# chariot_sensor.net
KiCad netlist of a schematic drawn in EAGLE
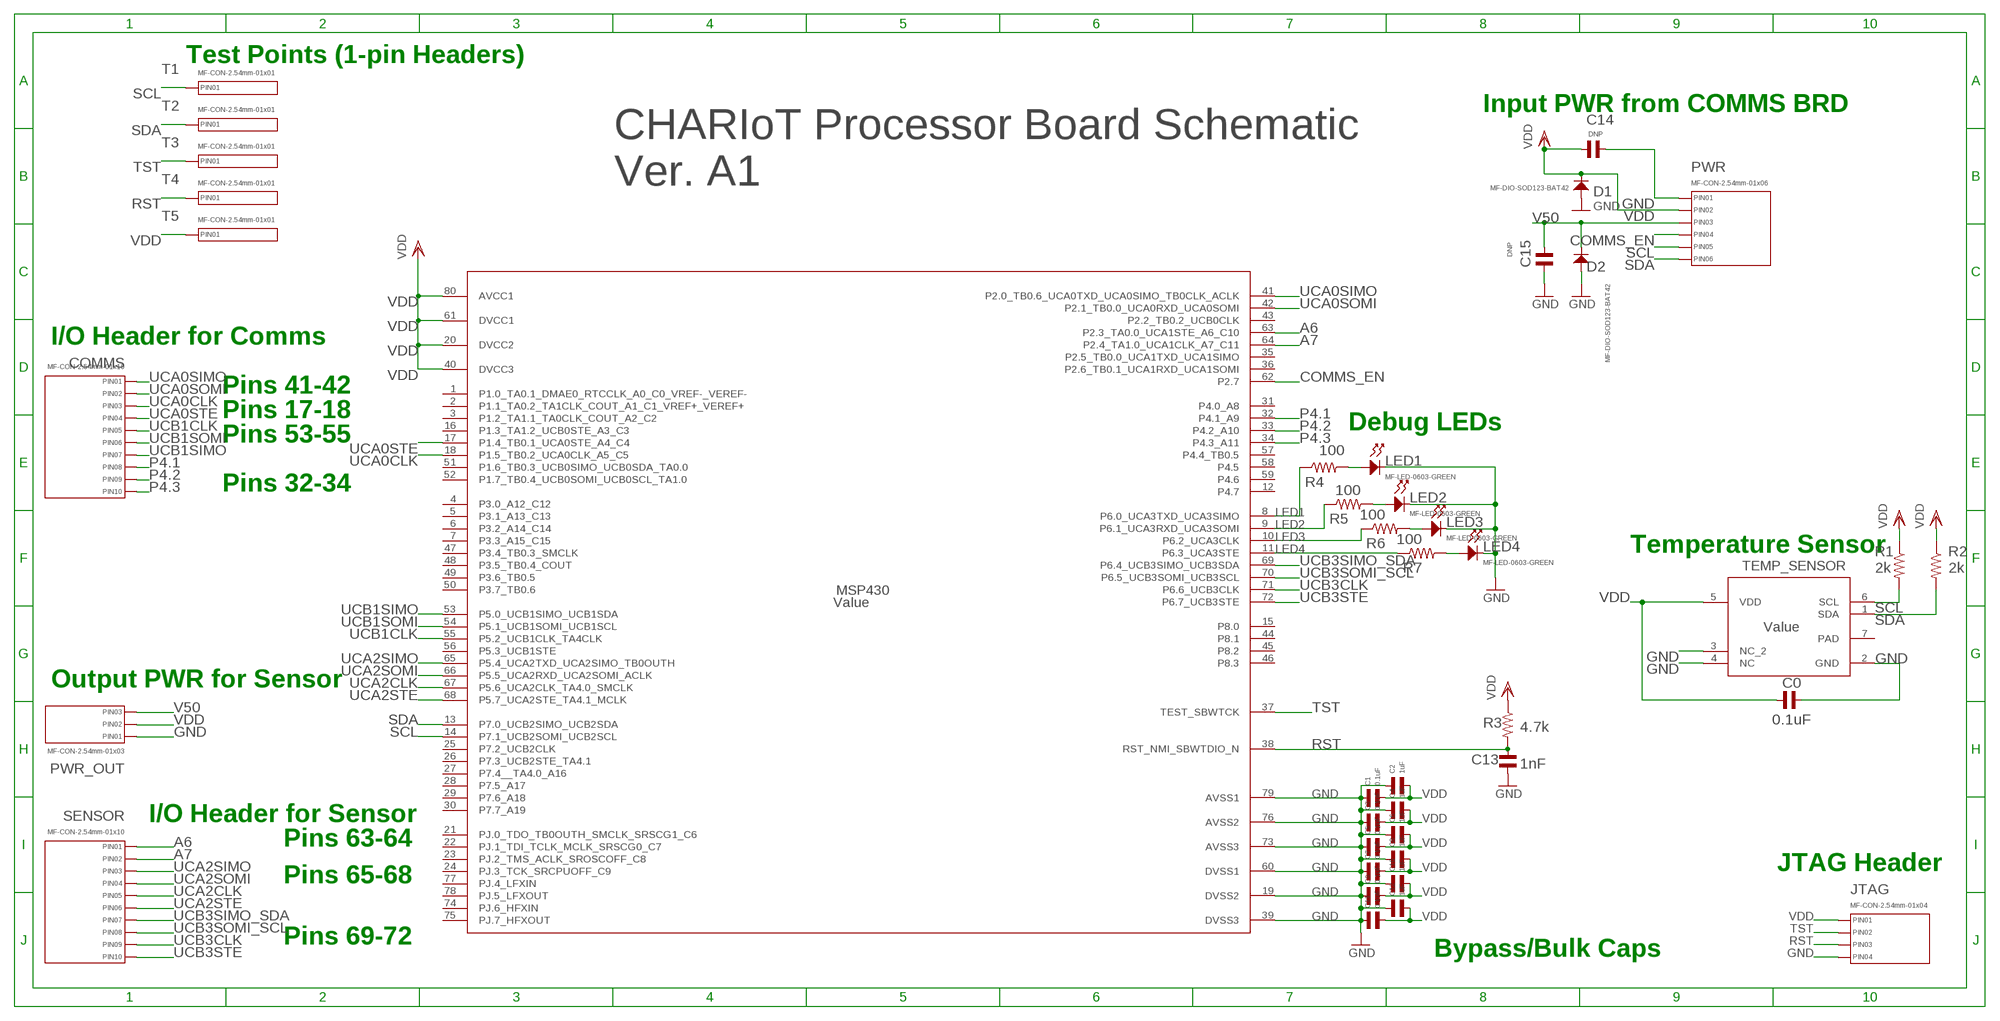
[diagram p0: schematic, sheet 1]

(export (version "E")
  (design (tool "Eeschema 10.0.6"))
  (components
    (comp (ref "C0")
      (value "0.1uF")
      (footprint "eagle-import:C0603")
      (libsource (lib "eagle-import") (part "CAPACITOR_NP_0603"))
    )
    (comp (ref "C1")
      (value "0.1uF")
      (footprint "eagle-import:C0603")
      (libsource (lib "eagle-import") (part "CAPACITOR_NP_0603"))
    )
    (comp (ref "C2")
      (value "1uF")
      (footprint "eagle-import:C0603")
      (libsource (lib "eagle-import") (part "CAPACITOR_NP_0603"))
    )
    (comp (ref "C3")
      (value "0.1uF")
      (footprint "eagle-import:C0603")
      (libsource (lib "eagle-import") (part "CAPACITOR_NP_0603"))
    )
    (comp (ref "C4")
      (value "1uF")
      (footprint "eagle-import:C0603")
      (libsource (lib "eagle-import") (part "CAPACITOR_NP_0603"))
    )
    (comp (ref "C5")
      (value "0.1uF")
      (footprint "eagle-import:C0603")
      (libsource (lib "eagle-import") (part "CAPACITOR_NP_0603"))
    )
    (comp (ref "C6")
      (value "1uF")
      (footprint "eagle-import:C0603")
      (libsource (lib "eagle-import") (part "CAPACITOR_NP_0603"))
    )
    (comp (ref "C7")
      (value "0.1uF")
      (footprint "eagle-import:C0603")
      (libsource (lib "eagle-import") (part "CAPACITOR_NP_0603"))
    )
    (comp (ref "C8")
      (value "1uF")
      (footprint "eagle-import:C0603")
      (libsource (lib "eagle-import") (part "CAPACITOR_NP_0603"))
    )
    (comp (ref "C9")
      (value "0.1uF")
      (footprint "eagle-import:C0603")
      (libsource (lib "eagle-import") (part "CAPACITOR_NP_0603"))
    )
    (comp (ref "C10")
      (value "1uF")
      (footprint "eagle-import:C0603")
      (libsource (lib "eagle-import") (part "CAPACITOR_NP_0603"))
    )
    (comp (ref "C11")
      (value "0.1uF")
      (footprint "eagle-import:C0603")
      (libsource (lib "eagle-import") (part "CAPACITOR_NP_0603"))
    )
    (comp (ref "C12")
      (value "1uF")
      (footprint "eagle-import:C0603")
      (libsource (lib "eagle-import") (part "CAPACITOR_NP_0603"))
    )
    (comp (ref "C13")
      (value "1nF")
      (footprint "eagle-import:C0603")
      (libsource (lib "eagle-import") (part "CAPACITOR_NP_0603"))
    )
    (comp (ref "C14")
      (value "DNP")
      (footprint "eagle-import:C0603")
      (libsource (lib "eagle-import") (part "CAPACITOR_NP_0603"))
    )
    (comp (ref "C15")
      (value "DNP")
      (footprint "eagle-import:C0603")
      (libsource (lib "eagle-import") (part "CAPACITOR_NP_0603"))
    )
    (comp (ref "COMMS")
      (value "MF-CON-2.54mm-01x10")
      (footprint "eagle-import:PTH_2.54MM_01X10")
      (fields (field (name "HOUSEPART") "YES"))
      (libsource (lib "eagle-import") (part "CON_01X10_PTH_2.54MM"))
    )
    (comp (ref "D1")
      (value "MF-DIO-SOD123-BAT42")
      (footprint "eagle-import:SOD-123")
      (fields (field (name "HOUSEPART") "YES"))
      (libsource (lib "eagle-import") (part "DIODES_SOD-123_BAT42"))
    )
    (comp (ref "D2")
      (value "MF-DIO-SOD123-BAT42")
      (footprint "eagle-import:SOD-123")
      (fields (field (name "HOUSEPART") "YES"))
      (libsource (lib "eagle-import") (part "DIODES_SOD-123_BAT42"))
    )
    (comp (ref "JTAG")
      (value "MF-CON-2.54mm-01x04")
      (footprint "eagle-import:PTH_2.54MM_01X04")
      (fields (field (name "HOUSEPART") "YES"))
      (libsource (lib "eagle-import") (part "CON_01X04_PTH_2.54MM"))
    )
    (comp (ref "LED1")
      (value "MF-LED-0603-GREEN")
      (footprint "eagle-import:LED0603")
      (fields (field (name "HOUSEPART") "YES"))
      (libsource (lib "eagle-import") (part "LED_SINGLE-0603-GREEN"))
    )
    (comp (ref "LED2")
      (value "MF-LED-0603-GREEN")
      (footprint "eagle-import:LED0603")
      (fields (field (name "HOUSEPART") "YES"))
      (libsource (lib "eagle-import") (part "LED_SINGLE-0603-GREEN"))
    )
    (comp (ref "LED3")
      (value "MF-LED-0603-GREEN")
      (footprint "eagle-import:LED0603")
      (fields (field (name "HOUSEPART") "YES"))
      (libsource (lib "eagle-import") (part "LED_SINGLE-0603-GREEN"))
    )
    (comp (ref "LED4")
      (value "MF-LED-0603-GREEN")
      (footprint "eagle-import:LED0603")
      (fields (field (name "HOUSEPART") "YES"))
      (libsource (lib "eagle-import") (part "LED_SINGLE-0603-GREEN"))
    )
    (comp (ref "MSP430")
      (value "Value")
      (footprint "eagle-import:PN0080A_N")
      (fields
        (field (name "MANUFACTURER") "Texas Instruments")
        (field (name "PARTNUMBER") "MSP430FR5994IPNR")
      )
      (libsource (lib "eagle-import") (part "MSP430FR5994IPNR"))
    )
    (comp (ref "PWR")
      (value "MF-CON-2.54mm-01x06")
      (footprint "eagle-import:PTH_2.54MM_01X06")
      (fields (field (name "HOUSEPART") "YES"))
      (libsource (lib "eagle-import") (part "CON_01X06_PTH_2.54MM"))
    )
    (comp (ref "PWR_OUT")
      (value "MF-CON-2.54mm-01x03")
      (footprint "eagle-import:PTH_2.54MM_01X03")
      (fields (field (name "HOUSEPART") "YES"))
      (libsource (lib "eagle-import") (part "CON_01X03_PTH_2.54MM"))
    )
    (comp (ref "R1")
      (value "2k")
      (footprint "eagle-import:R0603")
      (libsource (lib "eagle-import") (part "RESISTOR_0603"))
    )
    (comp (ref "R2")
      (value "2k")
      (footprint "eagle-import:R0603")
      (libsource (lib "eagle-import") (part "RESISTOR_0603"))
    )
    (comp (ref "R3")
      (value "4.7k")
      (footprint "eagle-import:R0603")
      (libsource (lib "eagle-import") (part "RESISTOR_0603"))
    )
    (comp (ref "R4")
      (value "100")
      (footprint "eagle-import:R0603")
      (libsource (lib "eagle-import") (part "RESISTOR_0603"))
    )
    (comp (ref "R5")
      (value "100")
      (footprint "eagle-import:R0603")
      (libsource (lib "eagle-import") (part "RESISTOR_0603"))
    )
    (comp (ref "R6")
      (value "100")
      (footprint "eagle-import:R0603")
      (libsource (lib "eagle-import") (part "RESISTOR_0603"))
    )
    (comp (ref "R7")
      (value "100")
      (footprint "eagle-import:R0603")
      (libsource (lib "eagle-import") (part "RESISTOR_0603"))
    )
    (comp (ref "SENSOR")
      (value "MF-CON-2.54mm-01x10")
      (footprint "eagle-import:PTH_2.54MM_01X10")
      (fields (field (name "HOUSEPART") "YES"))
      (libsource (lib "eagle-import") (part "CON_01X10_PTH_2.54MM"))
    )
    (comp (ref "T1")
      (value "MF-CON-2.54mm-01x01")
      (footprint "eagle-import:PTH_2.54MM_01X01")
      (fields (field (name "HOUSEPART") "YES"))
      (libsource (lib "eagle-import") (part "CON_01X01_PTH_2.54MM"))
    )
    (comp (ref "T2")
      (value "MF-CON-2.54mm-01x01")
      (footprint "eagle-import:PTH_2.54MM_01X01")
      (fields (field (name "HOUSEPART") "YES"))
      (libsource (lib "eagle-import") (part "CON_01X01_PTH_2.54MM"))
    )
    (comp (ref "T3")
      (value "MF-CON-2.54mm-01x01")
      (footprint "eagle-import:PTH_2.54MM_01X01")
      (fields (field (name "HOUSEPART") "YES"))
      (libsource (lib "eagle-import") (part "CON_01X01_PTH_2.54MM"))
    )
    (comp (ref "T4")
      (value "MF-CON-2.54mm-01x01")
      (footprint "eagle-import:PTH_2.54MM_01X01")
      (fields (field (name "HOUSEPART") "YES"))
      (libsource (lib "eagle-import") (part "CON_01X01_PTH_2.54MM"))
    )
    (comp (ref "T5")
      (value "MF-CON-2.54mm-01x01")
      (footprint "eagle-import:PTH_2.54MM_01X01")
      (fields (field (name "HOUSEPART") "YES"))
      (libsource (lib "eagle-import") (part "CON_01X01_PTH_2.54MM"))
    )
    (comp (ref "TEMP_SENSOR")
      (value "Value")
      (footprint "eagle-import:DMB0006A")
      (fields
        (field (name "ALTERNATEPARTNUMBER") "HDC1080DMBT")
        (field (name "MANUFACTURER") "Texas Instruments")
        (field (name "PARTNUMBER") "HDC1080DMBR")
      )
      (libsource (lib "eagle-import") (part "HDC1080DMBR"))
    )
  )
  (nets
    (net (code "1") (name "/A6") (class "Default")
      (node (ref "MSP430") (pin "63") (pinfunction "P2.3_TA0.0_UCA1STE_A6_C10_63") (pintype "bidirectional"))
      (node (ref "SENSOR") (pin "P$1") (pinfunction "PIN1_P$1") (pintype "bidirectional"))
    )
    (net (code "2") (name "/A7") (class "Default")
      (node (ref "MSP430") (pin "64") (pinfunction "P2.4_TA1.0_UCA1CLK_A7_C11_64") (pintype "bidirectional"))
      (node (ref "SENSOR") (pin "P$2") (pinfunction "PIN2_P$2") (pintype "bidirectional"))
    )
    (net (code "3") (name "/COMMS_EN") (class "Default")
      (node (ref "MSP430") (pin "62") (pinfunction "P2.7_62") (pintype "bidirectional"))
      (node (ref "PWR") (pin "P$4") (pinfunction "PIN4_P$4") (pintype "bidirectional"))
    )
    (net (code "4") (name "/LED1") (class "Default")
      (node (ref "MSP430") (pin "8") (pinfunction "P6.0_UCA3TXD_UCA3SIMO_8") (pintype "bidirectional"))
      (node (ref "R4") (pin "P$1") (pinfunction "P$1_P$1") (pintype "passive"))
    )
    (net (code "5") (name "/LED2") (class "Default")
      (node (ref "MSP430") (pin "9") (pinfunction "P6.1_UCA3RXD_UCA3SOMI_9") (pintype "bidirectional"))
      (node (ref "R5") (pin "P$1") (pinfunction "P$1_P$1") (pintype "passive"))
    )
    (net (code "6") (name "/LED3") (class "Default")
      (node (ref "MSP430") (pin "10") (pinfunction "P6.2_UCA3CLK_10") (pintype "bidirectional"))
      (node (ref "R6") (pin "P$1") (pinfunction "P$1_P$1") (pintype "passive"))
    )
    (net (code "7") (name "/LED4") (class "Default")
      (node (ref "MSP430") (pin "11") (pinfunction "P6.3_UCA3STE_11") (pintype "bidirectional"))
      (node (ref "R7") (pin "P$1") (pinfunction "P$1_P$1") (pintype "passive"))
    )
    (net (code "8") (name "/P4.1") (class "Default")
      (node (ref "COMMS") (pin "P$8") (pinfunction "PIN8_P$8") (pintype "bidirectional"))
      (node (ref "MSP430") (pin "32") (pinfunction "P4.1_A9_32") (pintype "bidirectional"))
    )
    (net (code "9") (name "/P4.2") (class "Default")
      (node (ref "COMMS") (pin "P$9") (pinfunction "PIN9_P$9") (pintype "bidirectional"))
      (node (ref "MSP430") (pin "33") (pinfunction "P4.2_A10_33") (pintype "bidirectional"))
    )
    (net (code "10") (name "/P4.3") (class "Default")
      (node (ref "COMMS") (pin "P$10") (pinfunction "PIN10_P$10") (pintype "bidirectional"))
      (node (ref "MSP430") (pin "34") (pinfunction "P4.3_A11_34") (pintype "bidirectional"))
    )
    (net (code "11") (name "/PAD") (class "Default")
      (node (ref "TEMP_SENSOR") (pin "7") (pinfunction "PAD_7") (pintype "power_in"))
    )
    (net (code "12") (name "/RST") (class "Default")
      (node (ref "C13") (pin "P$1") (pinfunction "P$1_P$1") (pintype "passive"))
      (node (ref "JTAG") (pin "P$3") (pinfunction "PIN3_P$3") (pintype "bidirectional"))
      (node (ref "MSP430") (pin "38") (pinfunction "RST_NMI_SBWTDIO_N_38") (pintype "bidirectional"))
      (node (ref "R3") (pin "P$2") (pinfunction "P$2_P$2") (pintype "passive"))
      (node (ref "T4") (pin "P$1") (pinfunction "PIN1_P$1") (pintype "bidirectional"))
    )
    (net (code "13") (name "/SCL") (class "Default")
      (node (ref "MSP430") (pin "14") (pinfunction "P7.1_UCB2SOMI_UCB2SCL_14") (pintype "bidirectional"))
      (node (ref "PWR") (pin "P$5") (pinfunction "PIN5_P$5") (pintype "bidirectional"))
      (node (ref "R1") (pin "P$2") (pinfunction "P$2_P$2") (pintype "passive"))
      (node (ref "T1") (pin "P$1") (pinfunction "PIN1_P$1") (pintype "bidirectional"))
      (node (ref "TEMP_SENSOR") (pin "6") (pinfunction "SCL_6") (pintype "open_collector"))
    )
    (net (code "14") (name "/SDA") (class "Default")
      (node (ref "MSP430") (pin "13") (pinfunction "P7.0_UCB2SIMO_UCB2SDA_13") (pintype "bidirectional"))
      (node (ref "PWR") (pin "P$6") (pinfunction "PIN6_P$6") (pintype "bidirectional"))
      (node (ref "R2") (pin "P$2") (pinfunction "P$2_P$2") (pintype "passive"))
      (node (ref "T2") (pin "P$1") (pinfunction "PIN1_P$1") (pintype "bidirectional"))
      (node (ref "TEMP_SENSOR") (pin "1") (pinfunction "SDA_1") (pintype "bidirectional"))
    )
    (net (code "15") (name "/TST") (class "Default")
      (node (ref "JTAG") (pin "P$2") (pinfunction "PIN2_P$2") (pintype "bidirectional"))
      (node (ref "MSP430") (pin "37") (pinfunction "TEST_SBWTCK_37") (pintype "input"))
      (node (ref "T3") (pin "P$1") (pinfunction "PIN1_P$1") (pintype "bidirectional"))
    )
    (net (code "16") (name "/UCA0CLK") (class "Default")
      (node (ref "COMMS") (pin "P$3") (pinfunction "PIN3_P$3") (pintype "bidirectional"))
      (node (ref "MSP430") (pin "18") (pinfunction "P1.5_TB0.2_UCA0CLK_A5_C5_18") (pintype "bidirectional"))
    )
    (net (code "17") (name "/UCA0SIMO") (class "Default")
      (node (ref "COMMS") (pin "P$1") (pinfunction "PIN1_P$1") (pintype "bidirectional"))
      (node (ref "MSP430") (pin "41") (pinfunction "P2.0_TB0.6_UCA0TXD_UCA0SIMO_TB0CLK_ACLK_41") (pintype "bidirectional"))
    )
    (net (code "18") (name "/UCA0SOMI") (class "Default")
      (node (ref "COMMS") (pin "P$2") (pinfunction "PIN2_P$2") (pintype "bidirectional"))
      (node (ref "MSP430") (pin "42") (pinfunction "P2.1_TB0.0_UCA0RXD_UCA0SOMI_42") (pintype "bidirectional"))
    )
    (net (code "19") (name "/UCA0STE") (class "Default")
      (node (ref "COMMS") (pin "P$4") (pinfunction "PIN4_P$4") (pintype "bidirectional"))
      (node (ref "MSP430") (pin "17") (pinfunction "P1.4_TB0.1_UCA0STE_A4_C4_17") (pintype "bidirectional"))
    )
    (net (code "20") (name "/UCA2CLK") (class "Default")
      (node (ref "MSP430") (pin "67") (pinfunction "P5.6_UCA2CLK_TA4.0_SMCLK_67") (pintype "bidirectional"))
      (node (ref "SENSOR") (pin "P$5") (pinfunction "PIN5_P$5") (pintype "bidirectional"))
    )
    (net (code "21") (name "/UCA2SIMO") (class "Default")
      (node (ref "MSP430") (pin "65") (pinfunction "P5.4_UCA2TXD_UCA2SIMO_TB0OUTH_65") (pintype "bidirectional"))
      (node (ref "SENSOR") (pin "P$3") (pinfunction "PIN3_P$3") (pintype "bidirectional"))
    )
    (net (code "22") (name "/UCA2SOMI") (class "Default")
      (node (ref "MSP430") (pin "66") (pinfunction "P5.5_UCA2RXD_UCA2SOMI_ACLK_66") (pintype "bidirectional"))
      (node (ref "SENSOR") (pin "P$4") (pinfunction "PIN4_P$4") (pintype "bidirectional"))
    )
    (net (code "23") (name "/UCA2STE") (class "Default")
      (node (ref "MSP430") (pin "68") (pinfunction "P5.7_UCA2STE_TA4.1_MCLK_68") (pintype "bidirectional"))
      (node (ref "SENSOR") (pin "P$6") (pinfunction "PIN6_P$6") (pintype "bidirectional"))
    )
    (net (code "24") (name "/UCB1CLK") (class "Default")
      (node (ref "COMMS") (pin "P$5") (pinfunction "PIN5_P$5") (pintype "bidirectional"))
      (node (ref "MSP430") (pin "55") (pinfunction "P5.2_UCB1CLK_TA4CLK_55") (pintype "bidirectional"))
    )
    (net (code "25") (name "/UCB1SIMO") (class "Default")
      (node (ref "COMMS") (pin "P$7") (pinfunction "PIN7_P$7") (pintype "bidirectional"))
      (node (ref "MSP430") (pin "53") (pinfunction "P5.0_UCB1SIMO_UCB1SDA_53") (pintype "bidirectional"))
    )
    (net (code "26") (name "/UCB1SOMI") (class "Default")
      (node (ref "COMMS") (pin "P$6") (pinfunction "PIN6_P$6") (pintype "bidirectional"))
      (node (ref "MSP430") (pin "54") (pinfunction "P5.1_UCB1SOMI_UCB1SCL_54") (pintype "bidirectional"))
    )
    (net (code "27") (name "/UCB3CLK") (class "Default")
      (node (ref "MSP430") (pin "71") (pinfunction "P6.6_UCB3CLK_71") (pintype "bidirectional"))
      (node (ref "SENSOR") (pin "P$9") (pinfunction "PIN9_P$9") (pintype "bidirectional"))
    )
    (net (code "28") (name "/UCB3SIMO_SDA") (class "Default")
      (node (ref "MSP430") (pin "69") (pinfunction "P6.4_UCB3SIMO_UCB3SDA_69") (pintype "bidirectional"))
      (node (ref "SENSOR") (pin "P$7") (pinfunction "PIN7_P$7") (pintype "bidirectional"))
    )
    (net (code "29") (name "/UCB3SOMI_SCL") (class "Default")
      (node (ref "MSP430") (pin "70") (pinfunction "P6.5_UCB3SOMI_UCB3SCL_70") (pintype "bidirectional"))
      (node (ref "SENSOR") (pin "P$8") (pinfunction "PIN8_P$8") (pintype "bidirectional"))
    )
    (net (code "30") (name "/UCB3STE") (class "Default")
      (node (ref "MSP430") (pin "72") (pinfunction "P6.7_UCB3STE_72") (pintype "bidirectional"))
      (node (ref "SENSOR") (pin "P$10") (pinfunction "PIN10_P$10") (pintype "bidirectional"))
    )
    (net (code "31") (name "/V50") (class "Default")
      (node (ref "C15") (pin "P$1") (pinfunction "P$1_P$1") (pintype "passive"))
      (node (ref "D2") (pin "CATHODE") (pinfunction "CATHODE_CATHODE") (pintype "bidirectional"))
      (node (ref "PWR") (pin "P$3") (pinfunction "PIN3_P$3") (pintype "bidirectional"))
      (node (ref "PWR_OUT") (pin "P$3") (pinfunction "PIN3_P$3") (pintype "bidirectional"))
    )
    (net (code "32") (name "GND") (class "Default")
      (node (ref "C0") (pin "P$2") (pinfunction "P$2_P$2") (pintype "passive"))
      (node (ref "C1") (pin "P$1") (pinfunction "P$1_P$1") (pintype "passive"))
      (node (ref "C10") (pin "P$1") (pinfunction "P$1_P$1") (pintype "passive"))
      (node (ref "C11") (pin "P$1") (pinfunction "P$1_P$1") (pintype "passive"))
      (node (ref "C12") (pin "P$1") (pinfunction "P$1_P$1") (pintype "passive"))
      (node (ref "C13") (pin "P$2") (pinfunction "P$2_P$2") (pintype "passive"))
      (node (ref "C14") (pin "P$2") (pinfunction "P$2_P$2") (pintype "passive"))
      (node (ref "C15") (pin "P$2") (pinfunction "P$2_P$2") (pintype "passive"))
      (node (ref "C2") (pin "P$1") (pinfunction "P$1_P$1") (pintype "passive"))
      (node (ref "C3") (pin "P$1") (pinfunction "P$1_P$1") (pintype "passive"))
      (node (ref "C4") (pin "P$1") (pinfunction "P$1_P$1") (pintype "passive"))
      (node (ref "C5") (pin "P$1") (pinfunction "P$1_P$1") (pintype "passive"))
      (node (ref "C6") (pin "P$1") (pinfunction "P$1_P$1") (pintype "passive"))
      (node (ref "C7") (pin "P$1") (pinfunction "P$1_P$1") (pintype "passive"))
      (node (ref "C8") (pin "P$1") (pinfunction "P$1_P$1") (pintype "passive"))
      (node (ref "C9") (pin "P$1") (pinfunction "P$1_P$1") (pintype "passive"))
      (node (ref "D1") (pin "ANODE") (pinfunction "ANODE_ANODE") (pintype "bidirectional"))
      (node (ref "D2") (pin "ANODE") (pinfunction "ANODE_ANODE") (pintype "bidirectional"))
      (node (ref "JTAG") (pin "P$4") (pinfunction "PIN4_P$4") (pintype "bidirectional"))
      (node (ref "LED1") (pin "CATHODE") (pinfunction "CATHODE_CATHODE") (pintype "power_in"))
      (node (ref "LED2") (pin "CATHODE") (pinfunction "CATHODE_CATHODE") (pintype "power_in"))
      (node (ref "LED3") (pin "CATHODE") (pinfunction "CATHODE_CATHODE") (pintype "power_in"))
      (node (ref "LED4") (pin "CATHODE") (pinfunction "CATHODE_CATHODE") (pintype "power_in"))
      (node (ref "MSP430") (pin "19") (pinfunction "DVSS2_19") (pintype "power_in"))
      (node (ref "MSP430") (pin "39") (pinfunction "DVSS3_39") (pintype "power_in"))
      (node (ref "MSP430") (pin "60") (pinfunction "DVSS1_60") (pintype "power_in"))
      (node (ref "MSP430") (pin "73") (pinfunction "AVSS3_73") (pintype "power_in"))
      (node (ref "MSP430") (pin "76") (pinfunction "AVSS2_76") (pintype "power_in"))
      (node (ref "MSP430") (pin "79") (pinfunction "AVSS1_79") (pintype "power_in"))
      (node (ref "PWR") (pin "P$1") (pinfunction "PIN1_P$1") (pintype "bidirectional"))
      (node (ref "PWR_OUT") (pin "P$1") (pinfunction "PIN1_P$1") (pintype "bidirectional"))
      (node (ref "TEMP_SENSOR") (pin "2") (pinfunction "GND_2") (pintype "power_in"))
      (node (ref "TEMP_SENSOR") (pin "3") (pinfunction "NC_2_3") (pintype "passive"))
      (node (ref "TEMP_SENSOR") (pin "4") (pinfunction "NC_4") (pintype "passive"))
    )
    (net (code "33") (name "Net-(LED1-PadANODE)") (class "Default")
      (node (ref "LED1") (pin "ANODE") (pinfunction "ANODE_ANODE") (pintype "power_in"))
      (node (ref "R4") (pin "P$2") (pinfunction "P$2_P$2") (pintype "passive"))
    )
    (net (code "34") (name "Net-(LED2-PadANODE)") (class "Default")
      (node (ref "LED2") (pin "ANODE") (pinfunction "ANODE_ANODE") (pintype "power_in"))
      (node (ref "R5") (pin "P$2") (pinfunction "P$2_P$2") (pintype "passive"))
    )
    (net (code "35") (name "Net-(LED3-PadANODE)") (class "Default")
      (node (ref "LED3") (pin "ANODE") (pinfunction "ANODE_ANODE") (pintype "power_in"))
      (node (ref "R6") (pin "P$2") (pinfunction "P$2_P$2") (pintype "passive"))
    )
    (net (code "36") (name "Net-(LED4-PadANODE)") (class "Default")
      (node (ref "LED4") (pin "ANODE") (pinfunction "ANODE_ANODE") (pintype "power_in"))
      (node (ref "R7") (pin "P$2") (pinfunction "P$2_P$2") (pintype "passive"))
    )
    (net (code "37") (name "VDD") (class "Default")
      (node (ref "C0") (pin "P$1") (pinfunction "P$1_P$1") (pintype "passive"))
      (node (ref "C1") (pin "P$2") (pinfunction "P$2_P$2") (pintype "passive"))
      (node (ref "C10") (pin "P$2") (pinfunction "P$2_P$2") (pintype "passive"))
      (node (ref "C11") (pin "P$2") (pinfunction "P$2_P$2") (pintype "passive"))
      (node (ref "C12") (pin "P$2") (pinfunction "P$2_P$2") (pintype "passive"))
      (node (ref "C14") (pin "P$1") (pinfunction "P$1_P$1") (pintype "passive"))
      (node (ref "C2") (pin "P$2") (pinfunction "P$2_P$2") (pintype "passive"))
      (node (ref "C3") (pin "P$2") (pinfunction "P$2_P$2") (pintype "passive"))
      (node (ref "C4") (pin "P$2") (pinfunction "P$2_P$2") (pintype "passive"))
      (node (ref "C5") (pin "P$2") (pinfunction "P$2_P$2") (pintype "passive"))
      (node (ref "C6") (pin "P$2") (pinfunction "P$2_P$2") (pintype "passive"))
      (node (ref "C7") (pin "P$2") (pinfunction "P$2_P$2") (pintype "passive"))
      (node (ref "C8") (pin "P$2") (pinfunction "P$2_P$2") (pintype "passive"))
      (node (ref "C9") (pin "P$2") (pinfunction "P$2_P$2") (pintype "passive"))
      (node (ref "D1") (pin "CATHODE") (pinfunction "CATHODE_CATHODE") (pintype "bidirectional"))
      (node (ref "JTAG") (pin "P$1") (pinfunction "PIN1_P$1") (pintype "bidirectional"))
      (node (ref "MSP430") (pin "20") (pinfunction "DVCC2_20") (pintype "power_in"))
      (node (ref "MSP430") (pin "40") (pinfunction "DVCC3_40") (pintype "power_in"))
      (node (ref "MSP430") (pin "61") (pinfunction "DVCC1_61") (pintype "power_in"))
      (node (ref "MSP430") (pin "80") (pinfunction "AVCC1_80") (pintype "power_in"))
      (node (ref "PWR") (pin "P$2") (pinfunction "PIN2_P$2") (pintype "bidirectional"))
      (node (ref "PWR_OUT") (pin "P$2") (pinfunction "PIN2_P$2") (pintype "bidirectional"))
      (node (ref "R1") (pin "P$1") (pinfunction "P$1_P$1") (pintype "passive"))
      (node (ref "R2") (pin "P$1") (pinfunction "P$1_P$1") (pintype "passive"))
      (node (ref "R3") (pin "P$1") (pinfunction "P$1_P$1") (pintype "passive"))
      (node (ref "T5") (pin "P$1") (pinfunction "PIN1_P$1") (pintype "bidirectional"))
      (node (ref "TEMP_SENSOR") (pin "5") (pinfunction "VDD_5") (pintype "power_in"))
    )
    (net (code "38") (name "unconnected-(MSP430-P1.0_TA0.1_DMAE0_RTCCLK_A0_C0_VREF-_VEREF--Pad1)") (class "Default")
      (node (ref "MSP430") (pin "1") (pinfunction "P1.0_TA0.1_DMAE0_RTCCLK_A0_C0_VREF-_VEREF-_1") (pintype "bidirectional"))
    )
    (net (code "39") (name "unconnected-(MSP430-P1.1_TA0.2_TA1CLK_COUT_A1_C1_VREF+_VEREF+-Pad2)") (class "Default")
      (node (ref "MSP430") (pin "2") (pinfunction "P1.1_TA0.2_TA1CLK_COUT_A1_C1_VREF+_VEREF+_2") (pintype "bidirectional"))
    )
    (net (code "40") (name "unconnected-(MSP430-P1.2_TA1.1_TA0CLK_COUT_A2_C2-Pad3)") (class "Default")
      (node (ref "MSP430") (pin "3") (pinfunction "P1.2_TA1.1_TA0CLK_COUT_A2_C2_3") (pintype "bidirectional"))
    )
    (net (code "41") (name "unconnected-(MSP430-P1.3_TA1.2_UCB0STE_A3_C3-Pad16)") (class "Default")
      (node (ref "MSP430") (pin "16") (pinfunction "P1.3_TA1.2_UCB0STE_A3_C3_16") (pintype "bidirectional"))
    )
    (net (code "42") (name "unconnected-(MSP430-P1.6_TB0.3_UCB0SIMO_UCB0SDA_TA0.0-Pad51)") (class "Default")
      (node (ref "MSP430") (pin "51") (pinfunction "P1.6_TB0.3_UCB0SIMO_UCB0SDA_TA0.0_51") (pintype "bidirectional"))
    )
    (net (code "43") (name "unconnected-(MSP430-P1.7_TB0.4_UCB0SOMI_UCB0SCL_TA1.0-Pad52)") (class "Default")
      (node (ref "MSP430") (pin "52") (pinfunction "P1.7_TB0.4_UCB0SOMI_UCB0SCL_TA1.0_52") (pintype "bidirectional"))
    )
    (net (code "44") (name "unconnected-(MSP430-P2.2_TB0.2_UCB0CLK-Pad43)") (class "Default")
      (node (ref "MSP430") (pin "43") (pinfunction "P2.2_TB0.2_UCB0CLK_43") (pintype "bidirectional"))
    )
    (net (code "45") (name "unconnected-(MSP430-P2.5_TB0.0_UCA1TXD_UCA1SIMO-Pad35)") (class "Default")
      (node (ref "MSP430") (pin "35") (pinfunction "P2.5_TB0.0_UCA1TXD_UCA1SIMO_35") (pintype "bidirectional"))
    )
    (net (code "46") (name "unconnected-(MSP430-P2.6_TB0.1_UCA1RXD_UCA1SOMI-Pad36)") (class "Default")
      (node (ref "MSP430") (pin "36") (pinfunction "P2.6_TB0.1_UCA1RXD_UCA1SOMI_36") (pintype "bidirectional"))
    )
    (net (code "47") (name "unconnected-(MSP430-P3.0_A12_C12-Pad4)") (class "Default")
      (node (ref "MSP430") (pin "4") (pinfunction "P3.0_A12_C12_4") (pintype "bidirectional"))
    )
    (net (code "48") (name "unconnected-(MSP430-P3.1_A13_C13-Pad5)") (class "Default")
      (node (ref "MSP430") (pin "5") (pinfunction "P3.1_A13_C13_5") (pintype "bidirectional"))
    )
    (net (code "49") (name "unconnected-(MSP430-P3.2_A14_C14-Pad6)") (class "Default")
      (node (ref "MSP430") (pin "6") (pinfunction "P3.2_A14_C14_6") (pintype "bidirectional"))
    )
    (net (code "50") (name "unconnected-(MSP430-P3.3_A15_C15-Pad7)") (class "Default")
      (node (ref "MSP430") (pin "7") (pinfunction "P3.3_A15_C15_7") (pintype "bidirectional"))
    )
    (net (code "51") (name "unconnected-(MSP430-P3.4_TB0.3_SMCLK-Pad47)") (class "Default")
      (node (ref "MSP430") (pin "47") (pinfunction "P3.4_TB0.3_SMCLK_47") (pintype "bidirectional"))
    )
    (net (code "52") (name "unconnected-(MSP430-P3.5_TB0.4_COUT-Pad48)") (class "Default")
      (node (ref "MSP430") (pin "48") (pinfunction "P3.5_TB0.4_COUT_48") (pintype "bidirectional"))
    )
    (net (code "53") (name "unconnected-(MSP430-P3.6_TB0.5-Pad49)") (class "Default")
      (node (ref "MSP430") (pin "49") (pinfunction "P3.6_TB0.5_49") (pintype "bidirectional"))
    )
    (net (code "54") (name "unconnected-(MSP430-P3.7_TB0.6-Pad50)") (class "Default")
      (node (ref "MSP430") (pin "50") (pinfunction "P3.7_TB0.6_50") (pintype "bidirectional"))
    )
    (net (code "55") (name "unconnected-(MSP430-P4.0_A8-Pad31)") (class "Default")
      (node (ref "MSP430") (pin "31") (pinfunction "P4.0_A8_31") (pintype "bidirectional"))
    )
    (net (code "56") (name "unconnected-(MSP430-P4.4_TB0.5-Pad57)") (class "Default")
      (node (ref "MSP430") (pin "57") (pinfunction "P4.4_TB0.5_57") (pintype "bidirectional"))
    )
    (net (code "57") (name "unconnected-(MSP430-P4.5-Pad58)") (class "Default")
      (node (ref "MSP430") (pin "58") (pinfunction "P4.5_58") (pintype "bidirectional"))
    )
    (net (code "58") (name "unconnected-(MSP430-P4.6-Pad59)") (class "Default")
      (node (ref "MSP430") (pin "59") (pinfunction "P4.6_59") (pintype "bidirectional"))
    )
    (net (code "59") (name "unconnected-(MSP430-P4.7-Pad12)") (class "Default")
      (node (ref "MSP430") (pin "12") (pinfunction "P4.7_12") (pintype "bidirectional"))
    )
    (net (code "60") (name "unconnected-(MSP430-P5.3_UCB1STE-Pad56)") (class "Default")
      (node (ref "MSP430") (pin "56") (pinfunction "P5.3_UCB1STE_56") (pintype "bidirectional"))
    )
    (net (code "61") (name "unconnected-(MSP430-P7.2_UCB2CLK-Pad25)") (class "Default")
      (node (ref "MSP430") (pin "25") (pinfunction "P7.2_UCB2CLK_25") (pintype "bidirectional"))
    )
    (net (code "62") (name "unconnected-(MSP430-P7.3_UCB2STE_TA4.1-Pad26)") (class "Default")
      (node (ref "MSP430") (pin "26") (pinfunction "P7.3_UCB2STE_TA4.1_26") (pintype "bidirectional"))
    )
    (net (code "63") (name "unconnected-(MSP430-P7.4__TA4.0_A16-Pad27)") (class "Default")
      (node (ref "MSP430") (pin "27") (pinfunction "P7.4__TA4.0_A16_27") (pintype "bidirectional"))
    )
    (net (code "64") (name "unconnected-(MSP430-P7.5_A17-Pad28)") (class "Default")
      (node (ref "MSP430") (pin "28") (pinfunction "P7.5_A17_28") (pintype "bidirectional"))
    )
    (net (code "65") (name "unconnected-(MSP430-P7.6_A18-Pad29)") (class "Default")
      (node (ref "MSP430") (pin "29") (pinfunction "P7.6_A18_29") (pintype "bidirectional"))
    )
    (net (code "66") (name "unconnected-(MSP430-P7.7_A19-Pad30)") (class "Default")
      (node (ref "MSP430") (pin "30") (pinfunction "P7.7_A19_30") (pintype "bidirectional"))
    )
    (net (code "67") (name "unconnected-(MSP430-P8.0-Pad15)") (class "Default")
      (node (ref "MSP430") (pin "15") (pinfunction "P8.0_15") (pintype "bidirectional"))
    )
    (net (code "68") (name "unconnected-(MSP430-P8.1-Pad44)") (class "Default")
      (node (ref "MSP430") (pin "44") (pinfunction "P8.1_44") (pintype "bidirectional"))
    )
    (net (code "69") (name "unconnected-(MSP430-P8.2-Pad45)") (class "Default")
      (node (ref "MSP430") (pin "45") (pinfunction "P8.2_45") (pintype "bidirectional"))
    )
    (net (code "70") (name "unconnected-(MSP430-P8.3-Pad46)") (class "Default")
      (node (ref "MSP430") (pin "46") (pinfunction "P8.3_46") (pintype "bidirectional"))
    )
    (net (code "71") (name "unconnected-(MSP430-PJ.0_TDO_TB0OUTH_SMCLK_SRSCG1_C6-Pad21)") (class "Default")
      (node (ref "MSP430") (pin "21") (pinfunction "PJ.0_TDO_TB0OUTH_SMCLK_SRSCG1_C6_21") (pintype "bidirectional"))
    )
    (net (code "72") (name "unconnected-(MSP430-PJ.1_TDI_TCLK_MCLK_SRSCG0_C7-Pad22)") (class "Default")
      (node (ref "MSP430") (pin "22") (pinfunction "PJ.1_TDI_TCLK_MCLK_SRSCG0_C7_22") (pintype "bidirectional"))
    )
    (net (code "73") (name "unconnected-(MSP430-PJ.2_TMS_ACLK_SROSCOFF_C8-Pad23)") (class "Default")
      (node (ref "MSP430") (pin "23") (pinfunction "PJ.2_TMS_ACLK_SROSCOFF_C8_23") (pintype "bidirectional"))
    )
    (net (code "74") (name "unconnected-(MSP430-PJ.3_TCK_SRCPUOFF_C9-Pad24)") (class "Default")
      (node (ref "MSP430") (pin "24") (pinfunction "PJ.3_TCK_SRCPUOFF_C9_24") (pintype "bidirectional"))
    )
    (net (code "75") (name "unconnected-(MSP430-PJ.4_LFXIN-Pad77)") (class "Default")
      (node (ref "MSP430") (pin "77") (pinfunction "PJ.4_LFXIN_77") (pintype "bidirectional"))
    )
    (net (code "76") (name "unconnected-(MSP430-PJ.5_LFXOUT-Pad78)") (class "Default")
      (node (ref "MSP430") (pin "78") (pinfunction "PJ.5_LFXOUT_78") (pintype "bidirectional"))
    )
    (net (code "77") (name "unconnected-(MSP430-PJ.6_HFXIN-Pad74)") (class "Default")
      (node (ref "MSP430") (pin "74") (pinfunction "PJ.6_HFXIN_74") (pintype "bidirectional"))
    )
    (net (code "78") (name "unconnected-(MSP430-PJ.7_HFXOUT-Pad75)") (class "Default")
      (node (ref "MSP430") (pin "75") (pinfunction "PJ.7_HFXOUT_75") (pintype "bidirectional"))
    )
  )
)
